# irisc.net
KiCad netlist of a schematic drawn in EAGLE
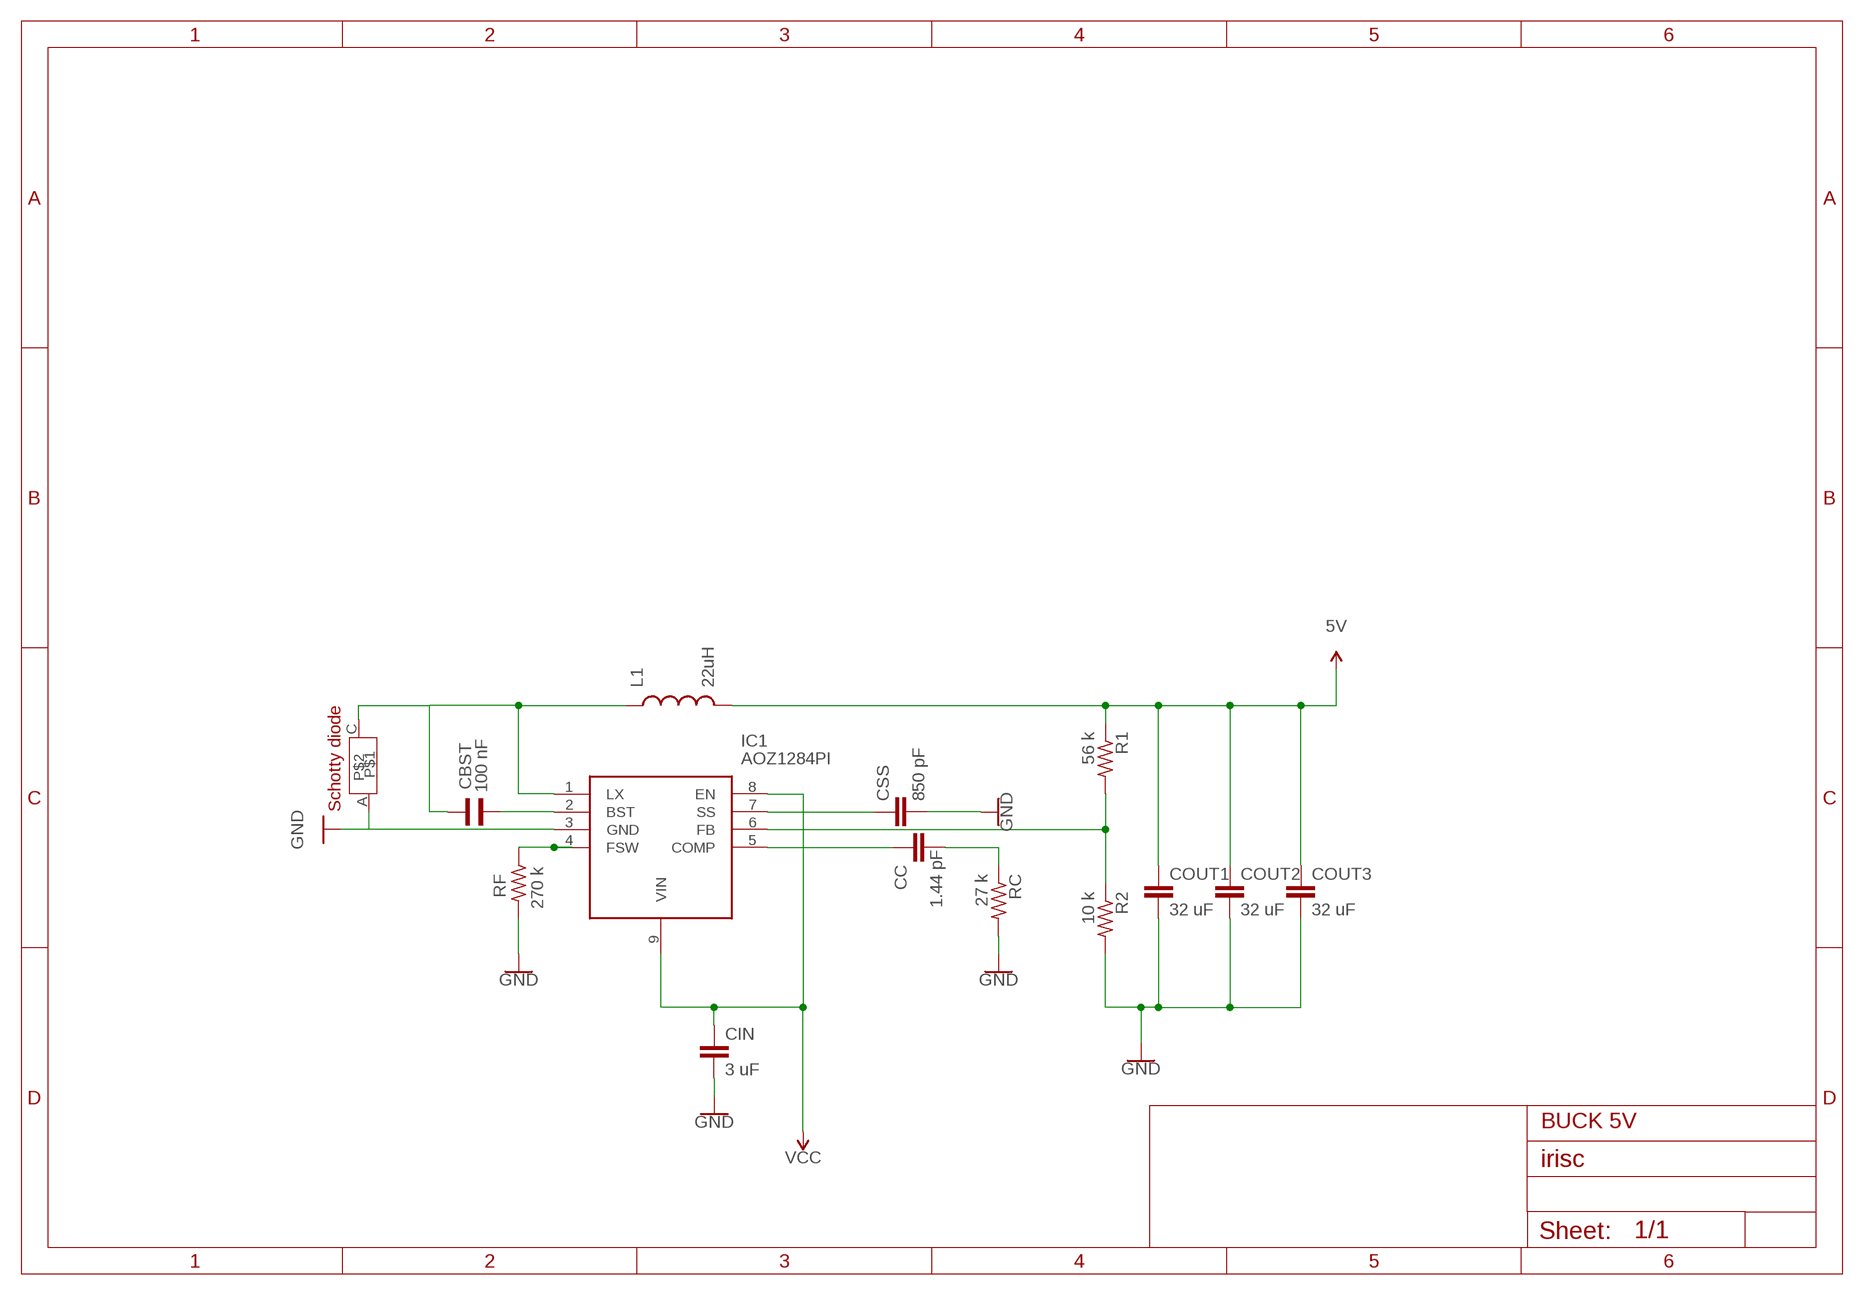
[diagram p0: schematic, sheet 1]

(export (version "E")
  (design (tool "Eeschema 10.0.6"))
  (components
    (comp (ref "CBST")
      (value "100 nF")
      (footprint "eagle-import:WCAP-CSGP_0805_WAVE")
      (fields (field (name "SPICEPREFIX") "C"))
      (libsource (lib "eagle-import") (part "WCAP-CSGP_0805_WAVE_885012006018"))
    )
    (comp (ref "CC")
      (value "1.44 pF")
      (footprint "eagle-import:C1206")
      (libsource (lib "eagle-import") (part "CC1206"))
    )
    (comp (ref "CIN")
      (value "3 uF")
      (footprint "eagle-import:C1210")
      (libsource (lib "eagle-import") (part "CC1210"))
    )
    (comp (ref "COUT1")
      (value "32 uF")
      (footprint "eagle-import:C1812")
      (libsource (lib "eagle-import") (part "CC1812"))
    )
    (comp (ref "COUT2")
      (value "32 uF")
      (footprint "eagle-import:C1812")
      (libsource (lib "eagle-import") (part "CC1812"))
    )
    (comp (ref "COUT3")
      (value "32 uF")
      (footprint "eagle-import:C1812")
      (libsource (lib "eagle-import") (part "CC1812"))
    )
    (comp (ref "CSS")
      (value "850 pF")
      (footprint "eagle-import:C0805")
      (libsource (lib "eagle-import") (part "C"))
    )
    (comp (ref "IC1")
      (value "AOZ1284PI")
      (footprint "eagle-import:SOIC127P600X170-9N")
      (libsource (lib "eagle-import") (part "AOZ1284PI"))
    )
    (comp (ref "L1")
      (value "22uH")
      (footprint "eagle-import:L0603")
      (libsource (lib "eagle-import") (part "INDUCTOR"))
    )
    (comp (ref "R1")
      (value "56 k")
      (footprint "eagle-import:0805-THM")
      (fields (field (name "SPICEPREFIX") "R"))
      (libsource (lib "eagle-import") (part "FLIPFLOP-RES"))
    )
    (comp (ref "R2")
      (value "10 k")
      (footprint "eagle-import:0805-THM")
      (fields (field (name "SPICEPREFIX") "R"))
      (libsource (lib "eagle-import") (part "FLIPFLOP-RES"))
    )
    (comp (ref "RC")
      (value "27 k")
      (footprint "eagle-import:0805-THM")
      (fields (field (name "SPICEPREFIX") "R"))
      (libsource (lib "eagle-import") (part "FLIPFLOP-RES"))
    )
    (comp (ref "RF")
      (value "270 k")
      (footprint "eagle-import:0805-THM")
      (fields (field (name "SPICEPREFIX") "R"))
      (libsource (lib "eagle-import") (part "FLIPFLOP-RES"))
    )
    (comp (ref "U$1")
      (value "SCHOTTY-DIODE-IRISC")
      (footprint "eagle-import:DO-214AC")
      (libsource (lib "eagle-import") (part "SCHOTTY-DIODE-IRISC"))
    )
  )
  (nets
    (net (code "1") (name "5V") (class "Default")
      (node (ref "COUT1") (pin "1") (pinfunction "1_1") (pintype "passive"))
      (node (ref "COUT2") (pin "1") (pinfunction "1_1") (pintype "passive"))
      (node (ref "COUT3") (pin "1") (pinfunction "1_1") (pintype "passive"))
      (node (ref "L1") (pin "2") (pinfunction "2_2") (pintype "passive"))
      (node (ref "R1") (pin "1") (pinfunction "1_1") (pintype "passive"))
    )
    (net (code "2") (name "GND") (class "Default")
      (node (ref "CIN") (pin "2") (pinfunction "2_2") (pintype "passive"))
      (node (ref "COUT1") (pin "2") (pinfunction "2_2") (pintype "passive"))
      (node (ref "COUT2") (pin "2") (pinfunction "2_2") (pintype "passive"))
      (node (ref "COUT3") (pin "2") (pinfunction "2_2") (pintype "passive"))
      (node (ref "CSS") (pin "2") (pinfunction "2_2") (pintype "passive"))
      (node (ref "IC1") (pin "3") (pinfunction "GND_3") (pintype "power_in"))
      (node (ref "R2") (pin "2") (pinfunction "2_2") (pintype "passive"))
      (node (ref "RC") (pin "2") (pinfunction "2_2") (pintype "passive"))
      (node (ref "RF") (pin "2") (pinfunction "2_2") (pintype "passive"))
      (node (ref "U$1") (pin "A") (pinfunction "P$1_A") (pintype "bidirectional"))
    )
    (net (code "3") (name "Net-(CC-Pad2)") (class "Default")
      (node (ref "CC") (pin "2") (pinfunction "2_2") (pintype "passive"))
      (node (ref "RC") (pin "1") (pinfunction "1_1") (pintype "passive"))
    )
    (net (code "4") (name "Net-(IC1-BST)") (class "Default")
      (node (ref "CBST") (pin "2") (pinfunction "2_2") (pintype "passive"))
      (node (ref "IC1") (pin "2") (pinfunction "BST_2") (pintype "bidirectional"))
    )
    (net (code "5") (name "Net-(IC1-COMP)") (class "Default")
      (node (ref "CC") (pin "1") (pinfunction "1_1") (pintype "passive"))
      (node (ref "IC1") (pin "5") (pinfunction "COMP_5") (pintype "bidirectional"))
    )
    (net (code "6") (name "Net-(IC1-FB)") (class "Default")
      (node (ref "IC1") (pin "6") (pinfunction "FB_6") (pintype "bidirectional"))
      (node (ref "R1") (pin "2") (pinfunction "2_2") (pintype "passive"))
      (node (ref "R2") (pin "1") (pinfunction "1_1") (pintype "passive"))
    )
    (net (code "7") (name "Net-(IC1-FSW)") (class "Default")
      (node (ref "IC1") (pin "4") (pinfunction "FSW_4") (pintype "bidirectional"))
      (node (ref "RF") (pin "1") (pinfunction "1_1") (pintype "passive"))
    )
    (net (code "8") (name "Net-(IC1-LX)") (class "Default")
      (node (ref "CBST") (pin "1") (pinfunction "1_1") (pintype "passive"))
      (node (ref "IC1") (pin "1") (pinfunction "LX_1") (pintype "bidirectional"))
      (node (ref "L1") (pin "1") (pinfunction "1_1") (pintype "passive"))
      (node (ref "U$1") (pin "C") (pinfunction "P$2_C") (pintype "bidirectional"))
    )
    (net (code "9") (name "Net-(IC1-SS)") (class "Default")
      (node (ref "CSS") (pin "1") (pinfunction "1_1") (pintype "passive"))
      (node (ref "IC1") (pin "7") (pinfunction "SS_7") (pintype "bidirectional"))
    )
    (net (code "10") (name "VCC") (class "Default")
      (node (ref "CIN") (pin "1") (pinfunction "1_1") (pintype "passive"))
      (node (ref "IC1") (pin "8") (pinfunction "EN_8") (pintype "bidirectional"))
      (node (ref "IC1") (pin "9") (pinfunction "VIN_9") (pintype "power_in"))
    )
  )
)
